# lcard_repeater.net
KiCad netlist of a schematic drawn in EAGLE
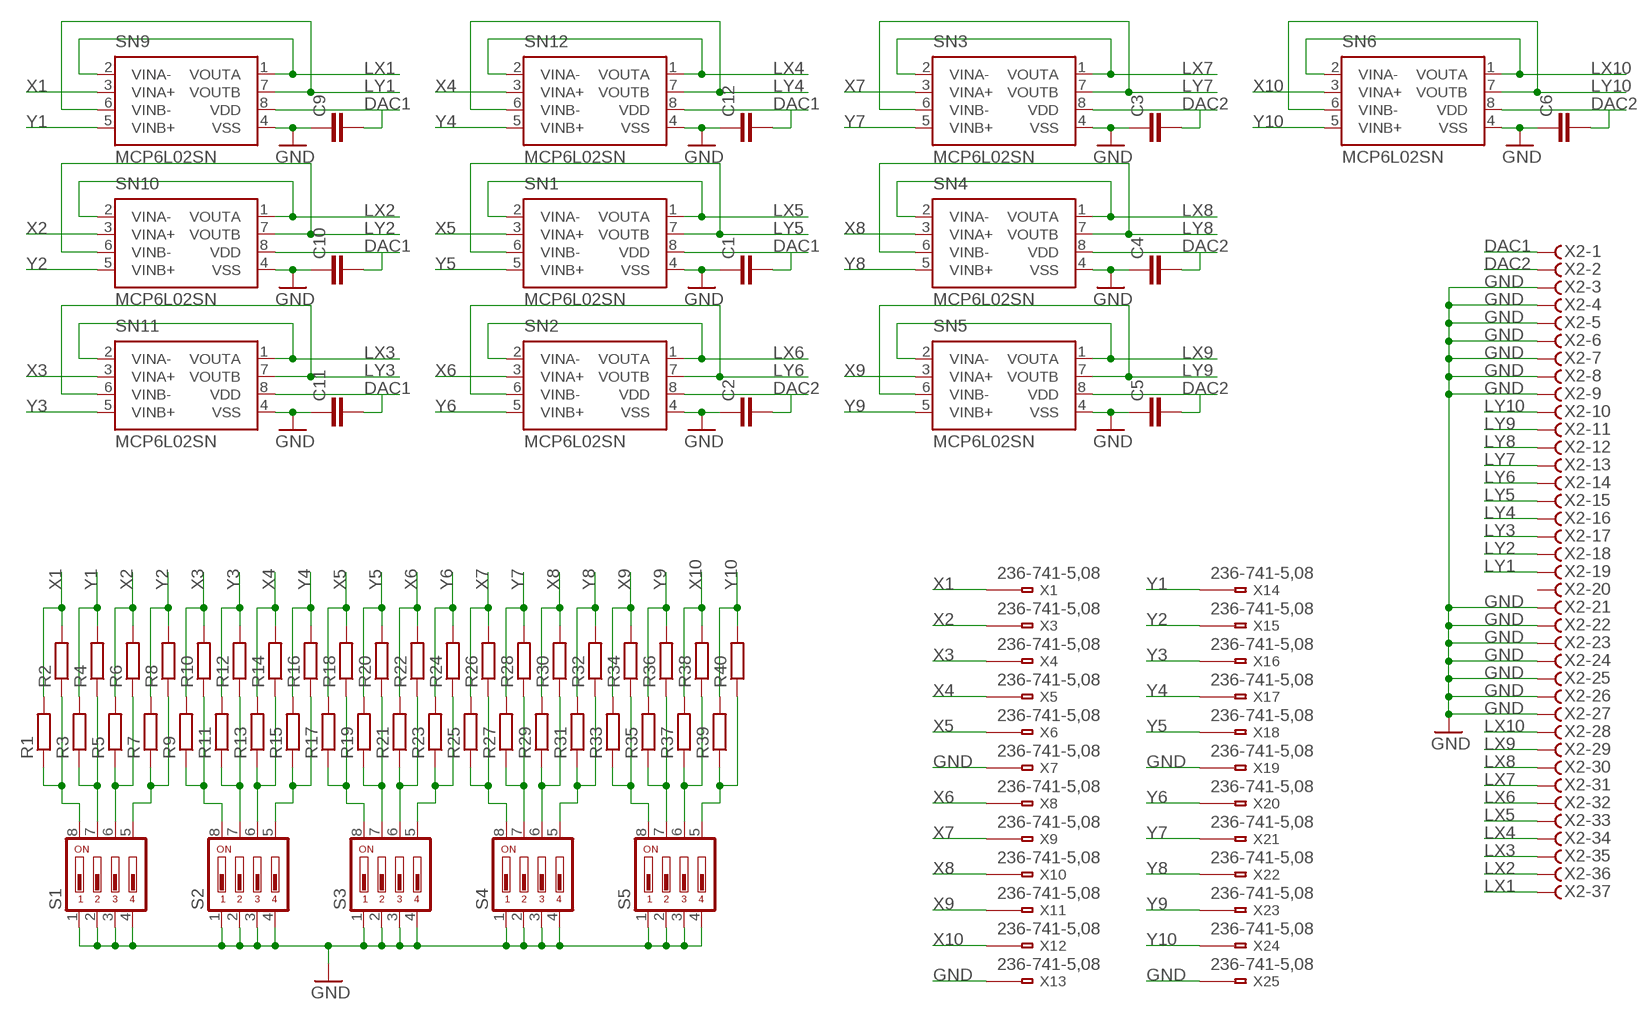
[diagram p0: schematic, sheet 1]

(export (version "E")
  (design (tool "Eeschema 10.0.6"))
  (components
    (comp (ref "C1")
      (value "C-EUC1206")
      (footprint "eagle-import:C1206")
      (libsource (lib "eagle-import") (part "C-EUC1206"))
    )
    (comp (ref "C2")
      (value "C-EUC1206")
      (footprint "eagle-import:C1206")
      (libsource (lib "eagle-import") (part "C-EUC1206"))
    )
    (comp (ref "C3")
      (value "C-EUC1206")
      (footprint "eagle-import:C1206")
      (libsource (lib "eagle-import") (part "C-EUC1206"))
    )
    (comp (ref "C4")
      (value "C-EUC1206")
      (footprint "eagle-import:C1206")
      (libsource (lib "eagle-import") (part "C-EUC1206"))
    )
    (comp (ref "C5")
      (value "C-EUC1206")
      (footprint "eagle-import:C1206")
      (libsource (lib "eagle-import") (part "C-EUC1206"))
    )
    (comp (ref "C6")
      (value "C-EUC1206")
      (footprint "eagle-import:C1206")
      (libsource (lib "eagle-import") (part "C-EUC1206"))
    )
    (comp (ref "C9")
      (value "C-EUC1206")
      (footprint "eagle-import:C1206")
      (libsource (lib "eagle-import") (part "C-EUC1206"))
    )
    (comp (ref "C10")
      (value "C-EUC1206")
      (footprint "eagle-import:C1206")
      (libsource (lib "eagle-import") (part "C-EUC1206"))
    )
    (comp (ref "C11")
      (value "C-EUC1206")
      (footprint "eagle-import:C1206")
      (libsource (lib "eagle-import") (part "C-EUC1206"))
    )
    (comp (ref "C12")
      (value "C-EUC1206")
      (footprint "eagle-import:C1206")
      (libsource (lib "eagle-import") (part "C-EUC1206"))
    )
    (comp (ref "R1")
      (value "R-EU_R1206")
      (footprint "eagle-import:R1206")
      (libsource (lib "eagle-import") (part "R-EU_R1206"))
    )
    (comp (ref "R2")
      (value "R-EU_R1206")
      (footprint "eagle-import:R1206")
      (libsource (lib "eagle-import") (part "R-EU_R1206"))
    )
    (comp (ref "R3")
      (value "R-EU_R1206")
      (footprint "eagle-import:R1206")
      (libsource (lib "eagle-import") (part "R-EU_R1206"))
    )
    (comp (ref "R4")
      (value "R-EU_R1206")
      (footprint "eagle-import:R1206")
      (libsource (lib "eagle-import") (part "R-EU_R1206"))
    )
    (comp (ref "R5")
      (value "R-EU_R1206")
      (footprint "eagle-import:R1206")
      (libsource (lib "eagle-import") (part "R-EU_R1206"))
    )
    (comp (ref "R6")
      (value "R-EU_R1206")
      (footprint "eagle-import:R1206")
      (libsource (lib "eagle-import") (part "R-EU_R1206"))
    )
    (comp (ref "R7")
      (value "R-EU_R1206")
      (footprint "eagle-import:R1206")
      (libsource (lib "eagle-import") (part "R-EU_R1206"))
    )
    (comp (ref "R8")
      (value "R-EU_R1206")
      (footprint "eagle-import:R1206")
      (libsource (lib "eagle-import") (part "R-EU_R1206"))
    )
    (comp (ref "R9")
      (value "R-EU_R1206")
      (footprint "eagle-import:R1206")
      (libsource (lib "eagle-import") (part "R-EU_R1206"))
    )
    (comp (ref "R10")
      (value "R-EU_R1206")
      (footprint "eagle-import:R1206")
      (libsource (lib "eagle-import") (part "R-EU_R1206"))
    )
    (comp (ref "R11")
      (value "R-EU_R1206")
      (footprint "eagle-import:R1206")
      (libsource (lib "eagle-import") (part "R-EU_R1206"))
    )
    (comp (ref "R12")
      (value "R-EU_R1206")
      (footprint "eagle-import:R1206")
      (libsource (lib "eagle-import") (part "R-EU_R1206"))
    )
    (comp (ref "R13")
      (value "R-EU_R1206")
      (footprint "eagle-import:R1206")
      (libsource (lib "eagle-import") (part "R-EU_R1206"))
    )
    (comp (ref "R14")
      (value "R-EU_R1206")
      (footprint "eagle-import:R1206")
      (libsource (lib "eagle-import") (part "R-EU_R1206"))
    )
    (comp (ref "R15")
      (value "R-EU_R1206")
      (footprint "eagle-import:R1206")
      (libsource (lib "eagle-import") (part "R-EU_R1206"))
    )
    (comp (ref "R16")
      (value "R-EU_R1206")
      (footprint "eagle-import:R1206")
      (libsource (lib "eagle-import") (part "R-EU_R1206"))
    )
    (comp (ref "R17")
      (value "R-EU_R1206")
      (footprint "eagle-import:R1206")
      (libsource (lib "eagle-import") (part "R-EU_R1206"))
    )
    (comp (ref "R18")
      (value "R-EU_R1206")
      (footprint "eagle-import:R1206")
      (libsource (lib "eagle-import") (part "R-EU_R1206"))
    )
    (comp (ref "R19")
      (value "R-EU_R1206")
      (footprint "eagle-import:R1206")
      (libsource (lib "eagle-import") (part "R-EU_R1206"))
    )
    (comp (ref "R20")
      (value "R-EU_R1206")
      (footprint "eagle-import:R1206")
      (libsource (lib "eagle-import") (part "R-EU_R1206"))
    )
    (comp (ref "R21")
      (value "R-EU_R1206")
      (footprint "eagle-import:R1206")
      (libsource (lib "eagle-import") (part "R-EU_R1206"))
    )
    (comp (ref "R22")
      (value "R-EU_R1206")
      (footprint "eagle-import:R1206")
      (libsource (lib "eagle-import") (part "R-EU_R1206"))
    )
    (comp (ref "R23")
      (value "R-EU_R1206")
      (footprint "eagle-import:R1206")
      (libsource (lib "eagle-import") (part "R-EU_R1206"))
    )
    (comp (ref "R24")
      (value "R-EU_R1206")
      (footprint "eagle-import:R1206")
      (libsource (lib "eagle-import") (part "R-EU_R1206"))
    )
    (comp (ref "R25")
      (value "R-EU_R1206")
      (footprint "eagle-import:R1206")
      (libsource (lib "eagle-import") (part "R-EU_R1206"))
    )
    (comp (ref "R26")
      (value "R-EU_R1206")
      (footprint "eagle-import:R1206")
      (libsource (lib "eagle-import") (part "R-EU_R1206"))
    )
    (comp (ref "R27")
      (value "R-EU_R1206")
      (footprint "eagle-import:R1206")
      (libsource (lib "eagle-import") (part "R-EU_R1206"))
    )
    (comp (ref "R28")
      (value "R-EU_R1206")
      (footprint "eagle-import:R1206")
      (libsource (lib "eagle-import") (part "R-EU_R1206"))
    )
    (comp (ref "R29")
      (value "R-EU_R1206")
      (footprint "eagle-import:R1206")
      (libsource (lib "eagle-import") (part "R-EU_R1206"))
    )
    (comp (ref "R30")
      (value "R-EU_R1206")
      (footprint "eagle-import:R1206")
      (libsource (lib "eagle-import") (part "R-EU_R1206"))
    )
    (comp (ref "R31")
      (value "R-EU_R1206")
      (footprint "eagle-import:R1206")
      (libsource (lib "eagle-import") (part "R-EU_R1206"))
    )
    (comp (ref "R32")
      (value "R-EU_R1206")
      (footprint "eagle-import:R1206")
      (libsource (lib "eagle-import") (part "R-EU_R1206"))
    )
    (comp (ref "R33")
      (value "R-EU_R1206")
      (footprint "eagle-import:R1206")
      (libsource (lib "eagle-import") (part "R-EU_R1206"))
    )
    (comp (ref "R34")
      (value "R-EU_R1206")
      (footprint "eagle-import:R1206")
      (libsource (lib "eagle-import") (part "R-EU_R1206"))
    )
    (comp (ref "R35")
      (value "R-EU_R1206")
      (footprint "eagle-import:R1206")
      (libsource (lib "eagle-import") (part "R-EU_R1206"))
    )
    (comp (ref "R36")
      (value "R-EU_R1206")
      (footprint "eagle-import:R1206")
      (libsource (lib "eagle-import") (part "R-EU_R1206"))
    )
    (comp (ref "R37")
      (value "R-EU_R1206")
      (footprint "eagle-import:R1206")
      (libsource (lib "eagle-import") (part "R-EU_R1206"))
    )
    (comp (ref "R38")
      (value "R-EU_R1206")
      (footprint "eagle-import:R1206")
      (libsource (lib "eagle-import") (part "R-EU_R1206"))
    )
    (comp (ref "R39")
      (value "R-EU_R1206")
      (footprint "eagle-import:R1206")
      (libsource (lib "eagle-import") (part "R-EU_R1206"))
    )
    (comp (ref "R40")
      (value "R-EU_R1206")
      (footprint "eagle-import:R1206")
      (libsource (lib "eagle-import") (part "R-EU_R1206"))
    )
    (comp (ref "S1")
      (value "DS04")
      (footprint "eagle-import:DS-04")
      (libsource (lib "eagle-import") (part "DS04"))
    )
    (comp (ref "S2")
      (value "DS04")
      (footprint "eagle-import:DS-04")
      (libsource (lib "eagle-import") (part "DS04"))
    )
    (comp (ref "S3")
      (value "DS04")
      (footprint "eagle-import:DS-04")
      (libsource (lib "eagle-import") (part "DS04"))
    )
    (comp (ref "S4")
      (value "DS04")
      (footprint "eagle-import:DS-04")
      (libsource (lib "eagle-import") (part "DS04"))
    )
    (comp (ref "S5")
      (value "DS04")
      (footprint "eagle-import:DS-04")
      (libsource (lib "eagle-import") (part "DS04"))
    )
    (comp (ref "SN1")
      (value "MCP6L02SN")
      (footprint "eagle-import:SOIC-08LG")
      (fields (field (name "MPN") "MXHV9910B"))
      (libsource (lib "eagle-import") (part "MCP6L02SN"))
    )
    (comp (ref "SN2")
      (value "MCP6L02SN")
      (footprint "eagle-import:SOIC-08LG")
      (fields (field (name "MPN") "MXHV9910B"))
      (libsource (lib "eagle-import") (part "MCP6L02SN"))
    )
    (comp (ref "SN3")
      (value "MCP6L02SN")
      (footprint "eagle-import:SOIC-08LG")
      (fields (field (name "MPN") "MXHV9910B"))
      (libsource (lib "eagle-import") (part "MCP6L02SN"))
    )
    (comp (ref "SN4")
      (value "MCP6L02SN")
      (footprint "eagle-import:SOIC-08LG")
      (fields (field (name "MPN") "MXHV9910B"))
      (libsource (lib "eagle-import") (part "MCP6L02SN"))
    )
    (comp (ref "SN5")
      (value "MCP6L02SN")
      (footprint "eagle-import:SOIC-08LG")
      (fields (field (name "MPN") "MXHV9910B"))
      (libsource (lib "eagle-import") (part "MCP6L02SN"))
    )
    (comp (ref "SN6")
      (value "MCP6L02SN")
      (footprint "eagle-import:SOIC-08LG")
      (fields (field (name "MPN") "MXHV9910B"))
      (libsource (lib "eagle-import") (part "MCP6L02SN"))
    )
    (comp (ref "SN9")
      (value "MCP6L02SN")
      (footprint "eagle-import:SOIC-08LG")
      (fields (field (name "MPN") "MXHV9910B"))
      (libsource (lib "eagle-import") (part "MCP6L02SN"))
    )
    (comp (ref "SN10")
      (value "MCP6L02SN")
      (footprint "eagle-import:SOIC-08LG")
      (fields (field (name "MPN") "MXHV9910B"))
      (libsource (lib "eagle-import") (part "MCP6L02SN"))
    )
    (comp (ref "SN11")
      (value "MCP6L02SN")
      (footprint "eagle-import:SOIC-08LG")
      (fields (field (name "MPN") "MXHV9910B"))
      (libsource (lib "eagle-import") (part "MCP6L02SN"))
    )
    (comp (ref "SN12")
      (value "MCP6L02SN")
      (footprint "eagle-import:SOIC-08LG")
      (fields (field (name "MPN") "MXHV9910B"))
      (libsource (lib "eagle-import") (part "MCP6L02SN"))
    )
    (comp (ref "X1")
      (value "236-741-5,08")
      (footprint "eagle-import:236-4XX")
      (libsource (lib "eagle-import") (part "236-5,08-741"))
    )
    (comp (ref "X2")
      (value "F37DS")
      (footprint "eagle-import:F37D")
      (libsource (lib "eagle-import") (part "F37?SD"))
    )
    (comp (ref "X3")
      (value "236-741-5,08")
      (footprint "eagle-import:236-4XX")
      (libsource (lib "eagle-import") (part "236-5,08-741"))
    )
    (comp (ref "X4")
      (value "236-741-5,08")
      (footprint "eagle-import:236-4XX")
      (libsource (lib "eagle-import") (part "236-5,08-741"))
    )
    (comp (ref "X5")
      (value "236-741-5,08")
      (footprint "eagle-import:236-4XX")
      (libsource (lib "eagle-import") (part "236-5,08-741"))
    )
    (comp (ref "X6")
      (value "236-741-5,08")
      (footprint "eagle-import:236-4XX")
      (libsource (lib "eagle-import") (part "236-5,08-741"))
    )
    (comp (ref "X7")
      (value "236-741-5,08")
      (footprint "eagle-import:236-4XX")
      (libsource (lib "eagle-import") (part "236-5,08-741"))
    )
    (comp (ref "X8")
      (value "236-741-5,08")
      (footprint "eagle-import:236-4XX")
      (libsource (lib "eagle-import") (part "236-5,08-741"))
    )
    (comp (ref "X9")
      (value "236-741-5,08")
      (footprint "eagle-import:236-4XX")
      (libsource (lib "eagle-import") (part "236-5,08-741"))
    )
    (comp (ref "X10")
      (value "236-741-5,08")
      (footprint "eagle-import:236-4XX")
      (libsource (lib "eagle-import") (part "236-5,08-741"))
    )
    (comp (ref "X11")
      (value "236-741-5,08")
      (footprint "eagle-import:236-4XX")
      (libsource (lib "eagle-import") (part "236-5,08-741"))
    )
    (comp (ref "X12")
      (value "236-741-5,08")
      (footprint "eagle-import:236-4XX")
      (libsource (lib "eagle-import") (part "236-5,08-741"))
    )
    (comp (ref "X13")
      (value "236-741-5,08")
      (footprint "eagle-import:236-4XX")
      (libsource (lib "eagle-import") (part "236-5,08-741"))
    )
    (comp (ref "X14")
      (value "236-741-5,08")
      (footprint "eagle-import:236-4XX")
      (libsource (lib "eagle-import") (part "236-5,08-741"))
    )
    (comp (ref "X15")
      (value "236-741-5,08")
      (footprint "eagle-import:236-4XX")
      (libsource (lib "eagle-import") (part "236-5,08-741"))
    )
    (comp (ref "X16")
      (value "236-741-5,08")
      (footprint "eagle-import:236-4XX")
      (libsource (lib "eagle-import") (part "236-5,08-741"))
    )
    (comp (ref "X17")
      (value "236-741-5,08")
      (footprint "eagle-import:236-4XX")
      (libsource (lib "eagle-import") (part "236-5,08-741"))
    )
    (comp (ref "X18")
      (value "236-741-5,08")
      (footprint "eagle-import:236-4XX")
      (libsource (lib "eagle-import") (part "236-5,08-741"))
    )
    (comp (ref "X19")
      (value "236-741-5,08")
      (footprint "eagle-import:236-4XX")
      (libsource (lib "eagle-import") (part "236-5,08-741"))
    )
    (comp (ref "X20")
      (value "236-741-5,08")
      (footprint "eagle-import:236-4XX")
      (libsource (lib "eagle-import") (part "236-5,08-741"))
    )
    (comp (ref "X21")
      (value "236-741-5,08")
      (footprint "eagle-import:236-4XX")
      (libsource (lib "eagle-import") (part "236-5,08-741"))
    )
    (comp (ref "X22")
      (value "236-741-5,08")
      (footprint "eagle-import:236-4XX")
      (libsource (lib "eagle-import") (part "236-5,08-741"))
    )
    (comp (ref "X23")
      (value "236-741-5,08")
      (footprint "eagle-import:236-4XX")
      (libsource (lib "eagle-import") (part "236-5,08-741"))
    )
    (comp (ref "X24")
      (value "236-741-5,08")
      (footprint "eagle-import:236-4XX")
      (libsource (lib "eagle-import") (part "236-5,08-741"))
    )
    (comp (ref "X25")
      (value "236-741-5,08")
      (footprint "eagle-import:236-4XX")
      (libsource (lib "eagle-import") (part "236-5,08-741"))
    )
  )
  (nets
    (net (code "1") (name "/DAC1") (class "Default")
      (node (ref "C1") (pin "2") (pinfunction "2_2") (pintype "passive"))
      (node (ref "C10") (pin "2") (pinfunction "2_2") (pintype "passive"))
      (node (ref "C11") (pin "2") (pinfunction "2_2") (pintype "passive"))
      (node (ref "C12") (pin "2") (pinfunction "2_2") (pintype "passive"))
      (node (ref "C9") (pin "2") (pinfunction "2_2") (pintype "passive"))
      (node (ref "SN1") (pin "8") (pinfunction "VDD_8") (pintype "power_in"))
      (node (ref "SN10") (pin "8") (pinfunction "VDD_8") (pintype "power_in"))
      (node (ref "SN11") (pin "8") (pinfunction "VDD_8") (pintype "power_in"))
      (node (ref "SN12") (pin "8") (pinfunction "VDD_8") (pintype "power_in"))
      (node (ref "SN9") (pin "8") (pinfunction "VDD_8") (pintype "power_in"))
      (node (ref "X2") (pin "1") (pinfunction "F_1") (pintype "passive"))
    )
    (net (code "2") (name "/DAC2") (class "Default")
      (node (ref "C2") (pin "2") (pinfunction "2_2") (pintype "passive"))
      (node (ref "C3") (pin "2") (pinfunction "2_2") (pintype "passive"))
      (node (ref "C4") (pin "2") (pinfunction "2_2") (pintype "passive"))
      (node (ref "C5") (pin "2") (pinfunction "2_2") (pintype "passive"))
      (node (ref "C6") (pin "2") (pinfunction "2_2") (pintype "passive"))
      (node (ref "SN2") (pin "8") (pinfunction "VDD_8") (pintype "power_in"))
      (node (ref "SN3") (pin "8") (pinfunction "VDD_8") (pintype "power_in"))
      (node (ref "SN4") (pin "8") (pinfunction "VDD_8") (pintype "power_in"))
      (node (ref "SN5") (pin "8") (pinfunction "VDD_8") (pintype "power_in"))
      (node (ref "SN6") (pin "8") (pinfunction "VDD_8") (pintype "power_in"))
      (node (ref "X2") (pin "2") (pinfunction "F_2") (pintype "passive"))
    )
    (net (code "3") (name "/LX1") (class "Default")
      (node (ref "SN9") (pin "1") (pinfunction "VOUTA_1") (pintype "passive"))
      (node (ref "SN9") (pin "2") (pinfunction "VINA-_2") (pintype "input"))
      (node (ref "X2") (pin "37") (pinfunction "F_37") (pintype "passive"))
    )
    (net (code "4") (name "/LX2") (class "Default")
      (node (ref "SN10") (pin "1") (pinfunction "VOUTA_1") (pintype "passive"))
      (node (ref "SN10") (pin "2") (pinfunction "VINA-_2") (pintype "input"))
      (node (ref "X2") (pin "36") (pinfunction "F_36") (pintype "passive"))
    )
    (net (code "5") (name "/LX3") (class "Default")
      (node (ref "SN11") (pin "1") (pinfunction "VOUTA_1") (pintype "passive"))
      (node (ref "SN11") (pin "2") (pinfunction "VINA-_2") (pintype "input"))
      (node (ref "X2") (pin "35") (pinfunction "F_35") (pintype "passive"))
    )
    (net (code "6") (name "/LX4") (class "Default")
      (node (ref "SN12") (pin "1") (pinfunction "VOUTA_1") (pintype "passive"))
      (node (ref "SN12") (pin "2") (pinfunction "VINA-_2") (pintype "input"))
      (node (ref "X2") (pin "34") (pinfunction "F_34") (pintype "passive"))
    )
    (net (code "7") (name "/LX5") (class "Default")
      (node (ref "SN1") (pin "1") (pinfunction "VOUTA_1") (pintype "passive"))
      (node (ref "SN1") (pin "2") (pinfunction "VINA-_2") (pintype "input"))
      (node (ref "X2") (pin "33") (pinfunction "F_33") (pintype "passive"))
    )
    (net (code "8") (name "/LX6") (class "Default")
      (node (ref "SN2") (pin "1") (pinfunction "VOUTA_1") (pintype "passive"))
      (node (ref "SN2") (pin "2") (pinfunction "VINA-_2") (pintype "input"))
      (node (ref "X2") (pin "32") (pinfunction "F_32") (pintype "passive"))
    )
    (net (code "9") (name "/LX7") (class "Default")
      (node (ref "SN3") (pin "1") (pinfunction "VOUTA_1") (pintype "passive"))
      (node (ref "SN3") (pin "2") (pinfunction "VINA-_2") (pintype "input"))
      (node (ref "X2") (pin "31") (pinfunction "F_31") (pintype "passive"))
    )
    (net (code "10") (name "/LX8") (class "Default")
      (node (ref "SN4") (pin "1") (pinfunction "VOUTA_1") (pintype "passive"))
      (node (ref "SN4") (pin "2") (pinfunction "VINA-_2") (pintype "input"))
      (node (ref "X2") (pin "30") (pinfunction "F_30") (pintype "passive"))
    )
    (net (code "11") (name "/LX9") (class "Default")
      (node (ref "SN5") (pin "1") (pinfunction "VOUTA_1") (pintype "passive"))
      (node (ref "SN5") (pin "2") (pinfunction "VINA-_2") (pintype "input"))
      (node (ref "X2") (pin "29") (pinfunction "F_29") (pintype "passive"))
    )
    (net (code "12") (name "/LX10") (class "Default")
      (node (ref "SN6") (pin "1") (pinfunction "VOUTA_1") (pintype "passive"))
      (node (ref "SN6") (pin "2") (pinfunction "VINA-_2") (pintype "input"))
      (node (ref "X2") (pin "28") (pinfunction "F_28") (pintype "passive"))
    )
    (net (code "13") (name "/LY1") (class "Default")
      (node (ref "SN9") (pin "6") (pinfunction "VINB-_6") (pintype "output"))
      (node (ref "SN9") (pin "7") (pinfunction "VOUTB_7") (pintype "input"))
      (node (ref "X2") (pin "19") (pinfunction "F_19") (pintype "passive"))
    )
    (net (code "14") (name "/LY2") (class "Default")
      (node (ref "SN10") (pin "6") (pinfunction "VINB-_6") (pintype "output"))
      (node (ref "SN10") (pin "7") (pinfunction "VOUTB_7") (pintype "input"))
      (node (ref "X2") (pin "18") (pinfunction "F_18") (pintype "passive"))
    )
    (net (code "15") (name "/LY3") (class "Default")
      (node (ref "SN11") (pin "6") (pinfunction "VINB-_6") (pintype "output"))
      (node (ref "SN11") (pin "7") (pinfunction "VOUTB_7") (pintype "input"))
      (node (ref "X2") (pin "17") (pinfunction "F_17") (pintype "passive"))
    )
    (net (code "16") (name "/LY4") (class "Default")
      (node (ref "SN12") (pin "6") (pinfunction "VINB-_6") (pintype "output"))
      (node (ref "SN12") (pin "7") (pinfunction "VOUTB_7") (pintype "input"))
      (node (ref "X2") (pin "16") (pinfunction "F_16") (pintype "passive"))
    )
    (net (code "17") (name "/LY5") (class "Default")
      (node (ref "SN1") (pin "6") (pinfunction "VINB-_6") (pintype "output"))
      (node (ref "SN1") (pin "7") (pinfunction "VOUTB_7") (pintype "input"))
      (node (ref "X2") (pin "15") (pinfunction "F_15") (pintype "passive"))
    )
    (net (code "18") (name "/LY6") (class "Default")
      (node (ref "SN2") (pin "6") (pinfunction "VINB-_6") (pintype "output"))
      (node (ref "SN2") (pin "7") (pinfunction "VOUTB_7") (pintype "input"))
      (node (ref "X2") (pin "14") (pinfunction "F_14") (pintype "passive"))
    )
    (net (code "19") (name "/LY7") (class "Default")
      (node (ref "SN3") (pin "6") (pinfunction "VINB-_6") (pintype "output"))
      (node (ref "SN3") (pin "7") (pinfunction "VOUTB_7") (pintype "input"))
      (node (ref "X2") (pin "13") (pinfunction "F_13") (pintype "passive"))
    )
    (net (code "20") (name "/LY8") (class "Default")
      (node (ref "SN4") (pin "6") (pinfunction "VINB-_6") (pintype "output"))
      (node (ref "SN4") (pin "7") (pinfunction "VOUTB_7") (pintype "input"))
      (node (ref "X2") (pin "12") (pinfunction "F_12") (pintype "passive"))
    )
    (net (code "21") (name "/LY9") (class "Default")
      (node (ref "SN5") (pin "6") (pinfunction "VINB-_6") (pintype "output"))
      (node (ref "SN5") (pin "7") (pinfunction "VOUTB_7") (pintype "input"))
      (node (ref "X2") (pin "11") (pinfunction "F_11") (pintype "passive"))
    )
    (net (code "22") (name "/LY10") (class "Default")
      (node (ref "SN6") (pin "6") (pinfunction "VINB-_6") (pintype "output"))
      (node (ref "SN6") (pin "7") (pinfunction "VOUTB_7") (pintype "input"))
      (node (ref "X2") (pin "10") (pinfunction "F_10") (pintype "passive"))
    )
    (net (code "23") (name "/X1") (class "Default")
      (node (ref "R1") (pin "2") (pinfunction "2_2") (pintype "passive"))
      (node (ref "R2") (pin "2") (pinfunction "2_2") (pintype "passive"))
      (node (ref "SN9") (pin "3") (pinfunction "VINA+_3") (pintype "input"))
      (node (ref "X1") (pin "1@2") (pinfunction "B1_1@2") (pintype "passive"))
    )
    (net (code "24") (name "/X2") (class "Default")
      (node (ref "R5") (pin "2") (pinfunction "2_2") (pintype "passive"))
      (node (ref "R6") (pin "2") (pinfunction "2_2") (pintype "passive"))
      (node (ref "SN10") (pin "3") (pinfunction "VINA+_3") (pintype "input"))
      (node (ref "X3") (pin "1@2") (pinfunction "B1_1@2") (pintype "passive"))
    )
    (net (code "25") (name "/X3") (class "Default")
      (node (ref "R10") (pin "2") (pinfunction "2_2") (pintype "passive"))
      (node (ref "R9") (pin "2") (pinfunction "2_2") (pintype "passive"))
      (node (ref "SN11") (pin "3") (pinfunction "VINA+_3") (pintype "input"))
      (node (ref "X4") (pin "1@2") (pinfunction "B1_1@2") (pintype "passive"))
    )
    (net (code "26") (name "/X4") (class "Default")
      (node (ref "R13") (pin "2") (pinfunction "2_2") (pintype "passive"))
      (node (ref "R14") (pin "2") (pinfunction "2_2") (pintype "passive"))
      (node (ref "SN12") (pin "3") (pinfunction "VINA+_3") (pintype "input"))
      (node (ref "X5") (pin "1@2") (pinfunction "B1_1@2") (pintype "passive"))
    )
    (net (code "27") (name "/X5") (class "Default")
      (node (ref "R17") (pin "2") (pinfunction "2_2") (pintype "passive"))
      (node (ref "R18") (pin "2") (pinfunction "2_2") (pintype "passive"))
      (node (ref "SN1") (pin "3") (pinfunction "VINA+_3") (pintype "input"))
      (node (ref "X6") (pin "1@2") (pinfunction "B1_1@2") (pintype "passive"))
    )
    (net (code "28") (name "/X6") (class "Default")
      (node (ref "R21") (pin "2") (pinfunction "2_2") (pintype "passive"))
      (node (ref "R22") (pin "2") (pinfunction "2_2") (pintype "passive"))
      (node (ref "SN2") (pin "3") (pinfunction "VINA+_3") (pintype "input"))
      (node (ref "X8") (pin "1@2") (pinfunction "B1_1@2") (pintype "passive"))
    )
    (net (code "29") (name "/X7") (class "Default")
      (node (ref "R25") (pin "2") (pinfunction "2_2") (pintype "passive"))
      (node (ref "R26") (pin "2") (pinfunction "2_2") (pintype "passive"))
      (node (ref "SN3") (pin "3") (pinfunction "VINA+_3") (pintype "input"))
      (node (ref "X9") (pin "1@2") (pinfunction "B1_1@2") (pintype "passive"))
    )
    (net (code "30") (name "/X8") (class "Default")
      (node (ref "R29") (pin "2") (pinfunction "2_2") (pintype "passive"))
      (node (ref "R30") (pin "2") (pinfunction "2_2") (pintype "passive"))
      (node (ref "SN4") (pin "3") (pinfunction "VINA+_3") (pintype "input"))
      (node (ref "X10") (pin "1@2") (pinfunction "B1_1@2") (pintype "passive"))
    )
    (net (code "31") (name "/X9") (class "Default")
      (node (ref "R33") (pin "2") (pinfunction "2_2") (pintype "passive"))
      (node (ref "R34") (pin "2") (pinfunction "2_2") (pintype "passive"))
      (node (ref "SN5") (pin "3") (pinfunction "VINA+_3") (pintype "input"))
      (node (ref "X11") (pin "1@2") (pinfunction "B1_1@2") (pintype "passive"))
    )
    (net (code "32") (name "/X10") (class "Default")
      (node (ref "R37") (pin "2") (pinfunction "2_2") (pintype "passive"))
      (node (ref "R38") (pin "2") (pinfunction "2_2") (pintype "passive"))
      (node (ref "SN6") (pin "3") (pinfunction "VINA+_3") (pintype "input"))
      (node (ref "X12") (pin "1@2") (pinfunction "B1_1@2") (pintype "passive"))
    )
    (net (code "33") (name "/Y1") (class "Default")
      (node (ref "R3") (pin "2") (pinfunction "2_2") (pintype "passive"))
      (node (ref "R4") (pin "2") (pinfunction "2_2") (pintype "passive"))
      (node (ref "SN9") (pin "5") (pinfunction "VINB+_5") (pintype "input"))
      (node (ref "X14") (pin "1@2") (pinfunction "B1_1@2") (pintype "passive"))
    )
    (net (code "34") (name "/Y2") (class "Default")
      (node (ref "R7") (pin "2") (pinfunction "2_2") (pintype "passive"))
      (node (ref "R8") (pin "2") (pinfunction "2_2") (pintype "passive"))
      (node (ref "SN10") (pin "5") (pinfunction "VINB+_5") (pintype "input"))
      (node (ref "X15") (pin "1@2") (pinfunction "B1_1@2") (pintype "passive"))
    )
    (net (code "35") (name "/Y3") (class "Default")
      (node (ref "R11") (pin "2") (pinfunction "2_2") (pintype "passive"))
      (node (ref "R12") (pin "2") (pinfunction "2_2") (pintype "passive"))
      (node (ref "SN11") (pin "5") (pinfunction "VINB+_5") (pintype "input"))
      (node (ref "X16") (pin "1@2") (pinfunction "B1_1@2") (pintype "passive"))
    )
    (net (code "36") (name "/Y4") (class "Default")
      (node (ref "R15") (pin "2") (pinfunction "2_2") (pintype "passive"))
      (node (ref "R16") (pin "2") (pinfunction "2_2") (pintype "passive"))
      (node (ref "SN12") (pin "5") (pinfunction "VINB+_5") (pintype "input"))
      (node (ref "X17") (pin "1@2") (pinfunction "B1_1@2") (pintype "passive"))
    )
    (net (code "37") (name "/Y5") (class "Default")
      (node (ref "R19") (pin "2") (pinfunction "2_2") (pintype "passive"))
      (node (ref "R20") (pin "2") (pinfunction "2_2") (pintype "passive"))
      (node (ref "SN1") (pin "5") (pinfunction "VINB+_5") (pintype "input"))
      (node (ref "X18") (pin "1@2") (pinfunction "B1_1@2") (pintype "passive"))
    )
    (net (code "38") (name "/Y6") (class "Default")
      (node (ref "R23") (pin "2") (pinfunction "2_2") (pintype "passive"))
      (node (ref "R24") (pin "2") (pinfunction "2_2") (pintype "passive"))
      (node (ref "SN2") (pin "5") (pinfunction "VINB+_5") (pintype "input"))
      (node (ref "X20") (pin "1@2") (pinfunction "B1_1@2") (pintype "passive"))
    )
    (net (code "39") (name "/Y7") (class "Default")
      (node (ref "R27") (pin "2") (pinfunction "2_2") (pintype "passive"))
      (node (ref "R28") (pin "2") (pinfunction "2_2") (pintype "passive"))
      (node (ref "SN3") (pin "5") (pinfunction "VINB+_5") (pintype "input"))
      (node (ref "X21") (pin "1@2") (pinfunction "B1_1@2") (pintype "passive"))
    )
    (net (code "40") (name "/Y8") (class "Default")
      (node (ref "R31") (pin "2") (pinfunction "2_2") (pintype "passive"))
      (node (ref "R32") (pin "2") (pinfunction "2_2") (pintype "passive"))
      (node (ref "SN4") (pin "5") (pinfunction "VINB+_5") (pintype "input"))
      (node (ref "X22") (pin "1@2") (pinfunction "B1_1@2") (pintype "passive"))
    )
    (net (code "41") (name "/Y9") (class "Default")
      (node (ref "R35") (pin "2") (pinfunction "2_2") (pintype "passive"))
      (node (ref "R36") (pin "2") (pinfunction "2_2") (pintype "passive"))
      (node (ref "SN5") (pin "5") (pinfunction "VINB+_5") (pintype "input"))
      (node (ref "X23") (pin "1@2") (pinfunction "B1_1@2") (pintype "passive"))
    )
    (net (code "42") (name "/Y10") (class "Default")
      (node (ref "R39") (pin "2") (pinfunction "2_2") (pintype "passive"))
      (node (ref "R40") (pin "2") (pinfunction "2_2") (pintype "passive"))
      (node (ref "SN6") (pin "5") (pinfunction "VINB+_5") (pintype "input"))
      (node (ref "X24") (pin "1@2") (pinfunction "B1_1@2") (pintype "passive"))
    )
    (net (code "43") (name "GND") (class "Default")
      (node (ref "C1") (pin "1") (pinfunction "1_1") (pintype "passive"))
      (node (ref "C10") (pin "1") (pinfunction "1_1") (pintype "passive"))
      (node (ref "C11") (pin "1") (pinfunction "1_1") (pintype "passive"))
      (node (ref "C12") (pin "1") (pinfunction "1_1") (pintype "passive"))
      (node (ref "C2") (pin "1") (pinfunction "1_1") (pintype "passive"))
      (node (ref "C3") (pin "1") (pinfunction "1_1") (pintype "passive"))
      (node (ref "C4") (pin "1") (pinfunction "1_1") (pintype "passive"))
      (node (ref "C5") (pin "1") (pinfunction "1_1") (pintype "passive"))
      (node (ref "C6") (pin "1") (pinfunction "1_1") (pintype "passive"))
      (node (ref "C9") (pin "1") (pinfunction "1_1") (pintype "passive"))
      (node (ref "S1") (pin "1") (pinfunction "1_1") (pintype "passive"))
      (node (ref "S1") (pin "2") (pinfunction "2_2") (pintype "passive"))
      (node (ref "S1") (pin "3") (pinfunction "3_3") (pintype "passive"))
      (node (ref "S1") (pin "4") (pinfunction "4_4") (pintype "passive"))
      (node (ref "S2") (pin "1") (pinfunction "1_1") (pintype "passive"))
      (node (ref "S2") (pin "2") (pinfunction "2_2") (pintype "passive"))
      (node (ref "S2") (pin "3") (pinfunction "3_3") (pintype "passive"))
      (node (ref "S2") (pin "4") (pinfunction "4_4") (pintype "passive"))
      (node (ref "S3") (pin "1") (pinfunction "1_1") (pintype "passive"))
      (node (ref "S3") (pin "2") (pinfunction "2_2") (pintype "passive"))
      (node (ref "S3") (pin "3") (pinfunction "3_3") (pintype "passive"))
      (node (ref "S3") (pin "4") (pinfunction "4_4") (pintype "passive"))
      (node (ref "S4") (pin "1") (pinfunction "1_1") (pintype "passive"))
      (node (ref "S4") (pin "2") (pinfunction "2_2") (pintype "passive"))
      (node (ref "S4") (pin "3") (pinfunction "3_3") (pintype "passive"))
      (node (ref "S4") (pin "4") (pinfunction "4_4") (pintype "passive"))
      (node (ref "S5") (pin "1") (pinfunction "1_1") (pintype "passive"))
      (node (ref "S5") (pin "2") (pinfunction "2_2") (pintype "passive"))
      (node (ref "S5") (pin "3") (pinfunction "3_3") (pintype "passive"))
      (node (ref "S5") (pin "4") (pinfunction "4_4") (pintype "passive"))
      (node (ref "SN1") (pin "4") (pinfunction "VSS_4") (pintype "power_in"))
      (node (ref "SN10") (pin "4") (pinfunction "VSS_4") (pintype "power_in"))
      (node (ref "SN11") (pin "4") (pinfunction "VSS_4") (pintype "power_in"))
      (node (ref "SN12") (pin "4") (pinfunction "VSS_4") (pintype "power_in"))
      (node (ref "SN2") (pin "4") (pinfunction "VSS_4") (pintype "power_in"))
      (node (ref "SN3") (pin "4") (pinfunction "VSS_4") (pintype "power_in"))
      (node (ref "SN4") (pin "4") (pinfunction "VSS_4") (pintype "power_in"))
      (node (ref "SN5") (pin "4") (pinfunction "VSS_4") (pintype "power_in"))
      (node (ref "SN6") (pin "4") (pinfunction "VSS_4") (pintype "power_in"))
      (node (ref "SN9") (pin "4") (pinfunction "VSS_4") (pintype "power_in"))
      (node (ref "X13") (pin "1@2") (pinfunction "B1_1@2") (pintype "passive"))
      (node (ref "X19") (pin "1@2") (pinfunction "B1_1@2") (pintype "passive"))
      (node (ref "X2") (pin "21") (pinfunction "F_21") (pintype "passive"))
      (node (ref "X2") (pin "22") (pinfunction "F_22") (pintype "passive"))
      (node (ref "X2") (pin "23") (pinfunction "F_23") (pintype "passive"))
      (node (ref "X2") (pin "24") (pinfunction "F_24") (pintype "passive"))
      (node (ref "X2") (pin "25") (pinfunction "F_25") (pintype "passive"))
      (node (ref "X2") (pin "26") (pinfunction "F_26") (pintype "passive"))
      (node (ref "X2") (pin "27") (pinfunction "F_27") (pintype "passive"))
      (node (ref "X2") (pin "3") (pinfunction "F_3") (pintype "passive"))
      (node (ref "X2") (pin "4") (pinfunction "F_4") (pintype "passive"))
      (node (ref "X2") (pin "5") (pinfunction "F_5") (pintype "passive"))
      (node (ref "X2") (pin "6") (pinfunction "F_6") (pintype "passive"))
      (node (ref "X2") (pin "7") (pinfunction "F_7") (pintype "passive"))
      (node (ref "X2") (pin "8") (pinfunction "F_8") (pintype "passive"))
      (node (ref "X2") (pin "9") (pinfunction "F_9") (pintype "passive"))
      (node (ref "X25") (pin "1@2") (pinfunction "B1_1@2") (pintype "passive"))
      (node (ref "X7") (pin "1@2") (pinfunction "B1_1@2") (pintype "passive"))
    )
    (net (code "44") (name "Net-(R1-Pad1)") (class "Default")
      (node (ref "R1") (pin "1") (pinfunction "1_1") (pintype "passive"))
      (node (ref "R2") (pin "1") (pinfunction "1_1") (pintype "passive"))
      (node (ref "S1") (pin "8") (pinfunction "8_8") (pintype "passive"))
    )
    (net (code "45") (name "Net-(R3-Pad1)") (class "Default")
      (node (ref "R3") (pin "1") (pinfunction "1_1") (pintype "passive"))
      (node (ref "R4") (pin "1") (pinfunction "1_1") (pintype "passive"))
      (node (ref "S1") (pin "7") (pinfunction "7_7") (pintype "passive"))
    )
    (net (code "46") (name "Net-(R5-Pad1)") (class "Default")
      (node (ref "R5") (pin "1") (pinfunction "1_1") (pintype "passive"))
      (node (ref "R6") (pin "1") (pinfunction "1_1") (pintype "passive"))
      (node (ref "S1") (pin "6") (pinfunction "6_6") (pintype "passive"))
    )
    (net (code "47") (name "Net-(R7-Pad1)") (class "Default")
      (node (ref "R7") (pin "1") (pinfunction "1_1") (pintype "passive"))
      (node (ref "R8") (pin "1") (pinfunction "1_1") (pintype "passive"))
      (node (ref "S1") (pin "5") (pinfunction "5_5") (pintype "passive"))
    )
    (net (code "48") (name "Net-(R10-Pad1)") (class "Default")
      (node (ref "R10") (pin "1") (pinfunction "1_1") (pintype "passive"))
      (node (ref "R9") (pin "1") (pinfunction "1_1") (pintype "passive"))
      (node (ref "S2") (pin "8") (pinfunction "8_8") (pintype "passive"))
    )
    (net (code "49") (name "Net-(R11-Pad1)") (class "Default")
      (node (ref "R11") (pin "1") (pinfunction "1_1") (pintype "passive"))
      (node (ref "R12") (pin "1") (pinfunction "1_1") (pintype "passive"))
      (node (ref "S2") (pin "7") (pinfunction "7_7") (pintype "passive"))
    )
    (net (code "50") (name "Net-(R13-Pad1)") (class "Default")
      (node (ref "R13") (pin "1") (pinfunction "1_1") (pintype "passive"))
      (node (ref "R14") (pin "1") (pinfunction "1_1") (pintype "passive"))
      (node (ref "S2") (pin "6") (pinfunction "6_6") (pintype "passive"))
    )
    (net (code "51") (name "Net-(R15-Pad1)") (class "Default")
      (node (ref "R15") (pin "1") (pinfunction "1_1") (pintype "passive"))
      (node (ref "R16") (pin "1") (pinfunction "1_1") (pintype "passive"))
      (node (ref "S2") (pin "5") (pinfunction "5_5") (pintype "passive"))
    )
    (net (code "52") (name "Net-(R17-Pad1)") (class "Default")
      (node (ref "R17") (pin "1") (pinfunction "1_1") (pintype "passive"))
      (node (ref "R18") (pin "1") (pinfunction "1_1") (pintype "passive"))
      (node (ref "S3") (pin "8") (pinfunction "8_8") (pintype "passive"))
    )
    (net (code "53") (name "Net-(R19-Pad1)") (class "Default")
      (node (ref "R19") (pin "1") (pinfunction "1_1") (pintype "passive"))
      (node (ref "R20") (pin "1") (pinfunction "1_1") (pintype "passive"))
      (node (ref "S3") (pin "7") (pinfunction "7_7") (pintype "passive"))
    )
    (net (code "54") (name "Net-(R21-Pad1)") (class "Default")
      (node (ref "R21") (pin "1") (pinfunction "1_1") (pintype "passive"))
      (node (ref "R22") (pin "1") (pinfunction "1_1") (pintype "passive"))
      (node (ref "S3") (pin "6") (pinfunction "6_6") (pintype "passive"))
    )
    (net (code "55") (name "Net-(R23-Pad1)") (class "Default")
      (node (ref "R23") (pin "1") (pinfunction "1_1") (pintype "passive"))
      (node (ref "R24") (pin "1") (pinfunction "1_1") (pintype "passive"))
      (node (ref "S3") (pin "5") (pinfunction "5_5") (pintype "passive"))
    )
    (net (code "56") (name "Net-(R25-Pad1)") (class "Default")
      (node (ref "R25") (pin "1") (pinfunction "1_1") (pintype "passive"))
      (node (ref "R26") (pin "1") (pinfunction "1_1") (pintype "passive"))
      (node (ref "S4") (pin "8") (pinfunction "8_8") (pintype "passive"))
    )
    (net (code "57") (name "Net-(R27-Pad1)") (class "Default")
      (node (ref "R27") (pin "1") (pinfunction "1_1") (pintype "passive"))
      (node (ref "R28") (pin "1") (pinfunction "1_1") (pintype "passive"))
      (node (ref "S4") (pin "7") (pinfunction "7_7") (pintype "passive"))
    )
    (net (code "58") (name "Net-(R29-Pad1)") (class "Default")
      (node (ref "R29") (pin "1") (pinfunction "1_1") (pintype "passive"))
      (node (ref "R30") (pin "1") (pinfunction "1_1") (pintype "passive"))
      (node (ref "S4") (pin "6") (pinfunction "6_6") (pintype "passive"))
    )
    (net (code "59") (name "Net-(R31-Pad1)") (class "Default")
      (node (ref "R31") (pin "1") (pinfunction "1_1") (pintype "passive"))
      (node (ref "R32") (pin "1") (pinfunction "1_1") (pintype "passive"))
      (node (ref "S4") (pin "5") (pinfunction "5_5") (pintype "passive"))
    )
    (net (code "60") (name "Net-(R33-Pad1)") (class "Default")
      (node (ref "R33") (pin "1") (pinfunction "1_1") (pintype "passive"))
      (node (ref "R34") (pin "1") (pinfunction "1_1") (pintype "passive"))
      (node (ref "S5") (pin "8") (pinfunction "8_8") (pintype "passive"))
    )
    (net (code "61") (name "Net-(R35-Pad1)") (class "Default")
      (node (ref "R35") (pin "1") (pinfunction "1_1") (pintype "passive"))
      (node (ref "R36") (pin "1") (pinfunction "1_1") (pintype "passive"))
      (node (ref "S5") (pin "7") (pinfunction "7_7") (pintype "passive"))
    )
    (net (code "62") (name "Net-(R37-Pad1)") (class "Default")
      (node (ref "R37") (pin "1") (pinfunction "1_1") (pintype "passive"))
      (node (ref "R38") (pin "1") (pinfunction "1_1") (pintype "passive"))
      (node (ref "S5") (pin "6") (pinfunction "6_6") (pintype "passive"))
    )
    (net (code "63") (name "Net-(R39-Pad1)") (class "Default")
      (node (ref "R39") (pin "1") (pinfunction "1_1") (pintype "passive"))
      (node (ref "R40") (pin "1") (pinfunction "1_1") (pintype "passive"))
      (node (ref "S5") (pin "5") (pinfunction "5_5") (pintype "passive"))
    )
    (net (code "64") (name "unconnected-(X1-A1-Pad1@1)") (class "Default")
      (node (ref "X1") (pin "1@1") (pinfunction "A1_1@1") (pintype "passive"))
    )
    (net (code "65") (name "unconnected-(X2M-F-Pad20)") (class "Default")
      (node (ref "X2") (pin "20") (pinfunction "F_20") (pintype "passive"))
    )
    (net (code "66") (name "unconnected-(X3-A1-Pad1@1)") (class "Default")
      (node (ref "X3") (pin "1@1") (pinfunction "A1_1@1") (pintype "passive"))
    )
    (net (code "67") (name "unconnected-(X4-A1-Pad1@1)") (class "Default")
      (node (ref "X4") (pin "1@1") (pinfunction "A1_1@1") (pintype "passive"))
    )
    (net (code "68") (name "unconnected-(X5-A1-Pad1@1)") (class "Default")
      (node (ref "X5") (pin "1@1") (pinfunction "A1_1@1") (pintype "passive"))
    )
    (net (code "69") (name "unconnected-(X6-A1-Pad1@1)") (class "Default")
      (node (ref "X6") (pin "1@1") (pinfunction "A1_1@1") (pintype "passive"))
    )
    (net (code "70") (name "unconnected-(X7-A1-Pad1@1)") (class "Default")
      (node (ref "X7") (pin "1@1") (pinfunction "A1_1@1") (pintype "passive"))
    )
    (net (code "71") (name "unconnected-(X8-A1-Pad1@1)") (class "Default")
      (node (ref "X8") (pin "1@1") (pinfunction "A1_1@1") (pintype "passive"))
    )
    (net (code "72") (name "unconnected-(X9-A1-Pad1@1)") (class "Default")
      (node (ref "X9") (pin "1@1") (pinfunction "A1_1@1") (pintype "passive"))
    )
    (net (code "73") (name "unconnected-(X10-A1-Pad1@1)") (class "Default")
      (node (ref "X10") (pin "1@1") (pinfunction "A1_1@1") (pintype "passive"))
    )
    (net (code "74") (name "unconnected-(X11-A1-Pad1@1)") (class "Default")
      (node (ref "X11") (pin "1@1") (pinfunction "A1_1@1") (pintype "passive"))
    )
    (net (code "75") (name "unconnected-(X12-A1-Pad1@1)") (class "Default")
      (node (ref "X12") (pin "1@1") (pinfunction "A1_1@1") (pintype "passive"))
    )
    (net (code "76") (name "unconnected-(X13-A1-Pad1@1)") (class "Default")
      (node (ref "X13") (pin "1@1") (pinfunction "A1_1@1") (pintype "passive"))
    )
    (net (code "77") (name "unconnected-(X14-A1-Pad1@1)") (class "Default")
      (node (ref "X14") (pin "1@1") (pinfunction "A1_1@1") (pintype "passive"))
    )
    (net (code "78") (name "unconnected-(X15-A1-Pad1@1)") (class "Default")
      (node (ref "X15") (pin "1@1") (pinfunction "A1_1@1") (pintype "passive"))
    )
    (net (code "79") (name "unconnected-(X16-A1-Pad1@1)") (class "Default")
      (node (ref "X16") (pin "1@1") (pinfunction "A1_1@1") (pintype "passive"))
    )
    (net (code "80") (name "unconnected-(X17-A1-Pad1@1)") (class "Default")
      (node (ref "X17") (pin "1@1") (pinfunction "A1_1@1") (pintype "passive"))
    )
    (net (code "81") (name "unconnected-(X18-A1-Pad1@1)") (class "Default")
      (node (ref "X18") (pin "1@1") (pinfunction "A1_1@1") (pintype "passive"))
    )
    (net (code "82") (name "unconnected-(X19-A1-Pad1@1)") (class "Default")
      (node (ref "X19") (pin "1@1") (pinfunction "A1_1@1") (pintype "passive"))
    )
    (net (code "83") (name "unconnected-(X20-A1-Pad1@1)") (class "Default")
      (node (ref "X20") (pin "1@1") (pinfunction "A1_1@1") (pintype "passive"))
    )
    (net (code "84") (name "unconnected-(X21-A1-Pad1@1)") (class "Default")
      (node (ref "X21") (pin "1@1") (pinfunction "A1_1@1") (pintype "passive"))
    )
    (net (code "85") (name "unconnected-(X22-A1-Pad1@1)") (class "Default")
      (node (ref "X22") (pin "1@1") (pinfunction "A1_1@1") (pintype "passive"))
    )
    (net (code "86") (name "unconnected-(X23-A1-Pad1@1)") (class "Default")
      (node (ref "X23") (pin "1@1") (pinfunction "A1_1@1") (pintype "passive"))
    )
    (net (code "87") (name "unconnected-(X24-A1-Pad1@1)") (class "Default")
      (node (ref "X24") (pin "1@1") (pinfunction "A1_1@1") (pintype "passive"))
    )
    (net (code "88") (name "unconnected-(X25-A1-Pad1@1)") (class "Default")
      (node (ref "X25") (pin "1@1") (pinfunction "A1_1@1") (pintype "passive"))
    )
  )
)
